# wooden_alarm_simple.net
KiCad netlist of a schematic drawn in EAGLE
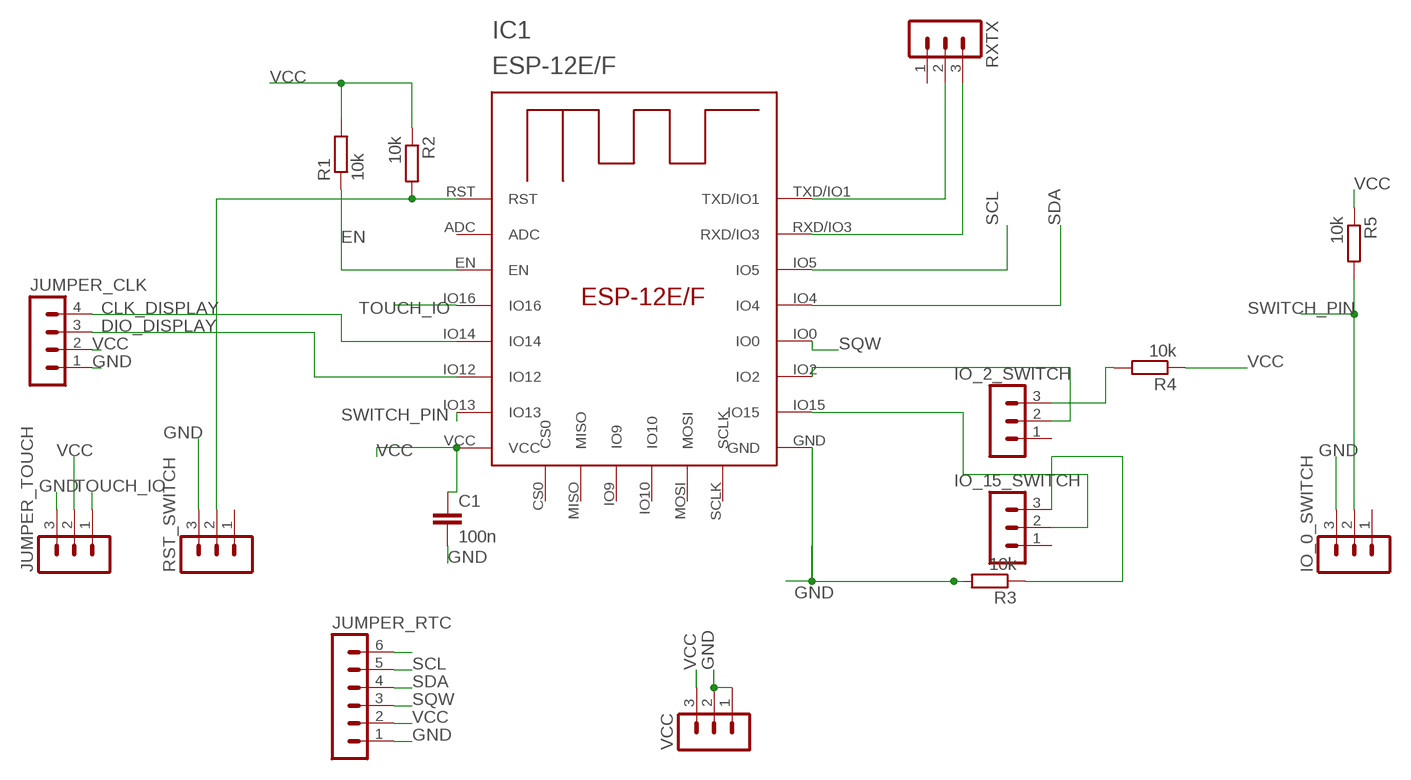
[diagram p0: schematic, sheet 1]

(export (version "E")
  (design (tool "Eeschema 10.0.6"))
  (components
    (comp (ref "C1")
      (value "100n")
      (footprint "eagle-import:C0805")
      (libsource (lib "eagle-import") (part "C-EUC0805"))
    )
    (comp (ref "IC1")
      (value "ESP-12E/F")
      (footprint "eagle-import:ESP-12E")
      (libsource (lib "eagle-import") (part "ESP-12E/F"))
    )
    (comp (ref "IO_0_SWITCH")
      (value "MA03-1")
      (footprint "eagle-import:MA03-1")
      (libsource (lib "eagle-import") (part "MA03-1"))
    )
    (comp (ref "IO_2_SWITCH")
      (value "MA03-1")
      (footprint "eagle-import:MA03-1")
      (libsource (lib "eagle-import") (part "MA03-1"))
    )
    (comp (ref "IO_15_SWITCH")
      (value "MA03-1")
      (footprint "eagle-import:MA03-1")
      (libsource (lib "eagle-import") (part "MA03-1"))
    )
    (comp (ref "JUMPER_CLK")
      (value "MA04-1")
      (footprint "eagle-import:MA04-1")
      (libsource (lib "eagle-import") (part "MA04-1"))
    )
    (comp (ref "JUMPER_RTC")
      (value "MA06-1")
      (footprint "eagle-import:MA06-1")
      (libsource (lib "eagle-import") (part "MA06-1"))
    )
    (comp (ref "JUMPER_TOUCH")
      (value "MA03-1")
      (footprint "eagle-import:MA03-1")
      (libsource (lib "eagle-import") (part "MA03-1"))
    )
    (comp (ref "R1")
      (value "10k")
      (footprint "eagle-import:R0805")
      (libsource (lib "eagle-import") (part "R-EU_R0805"))
    )
    (comp (ref "R2")
      (value "10k")
      (footprint "eagle-import:R0805")
      (libsource (lib "eagle-import") (part "R-EU_R0805"))
    )
    (comp (ref "R3")
      (value "10k")
      (footprint "eagle-import:R0805")
      (libsource (lib "eagle-import") (part "R-EU_R0805"))
    )
    (comp (ref "R4")
      (value "10k")
      (footprint "eagle-import:R0805")
      (libsource (lib "eagle-import") (part "R-EU_R0805"))
    )
    (comp (ref "R5")
      (value "10k")
      (footprint "eagle-import:R0805")
      (libsource (lib "eagle-import") (part "R-EU_R0805"))
    )
    (comp (ref "RST_SWITCH")
      (value "MA03-1")
      (footprint "eagle-import:MA03-1")
      (libsource (lib "eagle-import") (part "MA03-1"))
    )
    (comp (ref "RXTX")
      (value "MA03-1")
      (footprint "eagle-import:MA03-1")
      (libsource (lib "eagle-import") (part "MA03-1"))
    )
    (comp (ref "VCC")
      (value "MA03-1")
      (footprint "eagle-import:MA03-1")
      (libsource (lib "eagle-import") (part "MA03-1"))
    )
  )
  (nets
    (net (code "1") (name "/CLK_DISPLAY") (class "Default")
      (node (ref "IC1") (pin "IO14") (pinfunction "IO14_IO14") (pintype "bidirectional"))
      (node (ref "JUMPER_CLK") (pin "4") (pinfunction "4_4") (pintype "passive"))
    )
    (net (code "2") (name "/DIO_DISPLAY") (class "Default")
      (node (ref "IC1") (pin "IO12") (pinfunction "IO12_IO12") (pintype "bidirectional"))
      (node (ref "JUMPER_CLK") (pin "3") (pinfunction "3_3") (pintype "passive"))
    )
    (net (code "3") (name "/EN") (class "Default")
      (node (ref "IC1") (pin "EN") (pinfunction "EN_EN") (pintype "bidirectional"))
      (node (ref "R1") (pin "1") (pinfunction "1_1") (pintype "passive"))
    )
    (net (code "4") (name "/GND") (class "Default")
      (node (ref "C1") (pin "2") (pinfunction "2_2") (pintype "passive"))
      (node (ref "IC1") (pin "GND") (pinfunction "GND_GND") (pintype "power_in"))
      (node (ref "IO_0_SWITCH") (pin "3") (pinfunction "3_3") (pintype "passive"))
      (node (ref "JUMPER_CLK") (pin "1") (pinfunction "1_1") (pintype "passive"))
      (node (ref "JUMPER_RTC") (pin "1") (pinfunction "1_1") (pintype "passive"))
      (node (ref "JUMPER_TOUCH") (pin "3") (pinfunction "3_3") (pintype "passive"))
      (node (ref "R3") (pin "2") (pinfunction "2_2") (pintype "passive"))
      (node (ref "RST_SWITCH") (pin "3") (pinfunction "3_3") (pintype "passive"))
      (node (ref "VCC") (pin "1") (pinfunction "1_1") (pintype "passive"))
      (node (ref "VCC") (pin "2") (pinfunction "2_2") (pintype "passive"))
    )
    (net (code "5") (name "/SCL") (class "Default")
      (node (ref "IC1") (pin "IO5") (pinfunction "IO5_IO5") (pintype "bidirectional"))
      (node (ref "JUMPER_RTC") (pin "5") (pinfunction "5_5") (pintype "passive"))
    )
    (net (code "6") (name "/SDA") (class "Default")
      (node (ref "IC1") (pin "IO4") (pinfunction "IO4_IO4") (pintype "bidirectional"))
      (node (ref "JUMPER_RTC") (pin "4") (pinfunction "4_4") (pintype "passive"))
    )
    (net (code "7") (name "/SQW") (class "Default")
      (node (ref "IC1") (pin "IO0") (pinfunction "IO0_IO0") (pintype "bidirectional"))
      (node (ref "JUMPER_RTC") (pin "3") (pinfunction "3_3") (pintype "passive"))
    )
    (net (code "8") (name "/SWITCH_PIN") (class "Default")
      (node (ref "IC1") (pin "IO13") (pinfunction "IO13_IO13") (pintype "bidirectional"))
      (node (ref "IO_0_SWITCH") (pin "2") (pinfunction "2_2") (pintype "passive"))
      (node (ref "R5") (pin "2") (pinfunction "2_2") (pintype "passive"))
    )
    (net (code "9") (name "/TOUCH_IO") (class "Default")
      (node (ref "IC1") (pin "IO16") (pinfunction "IO16_IO16") (pintype "bidirectional"))
      (node (ref "JUMPER_TOUCH") (pin "1") (pinfunction "1_1") (pintype "passive"))
    )
    (net (code "10") (name "/VCC") (class "Default")
      (node (ref "C1") (pin "1") (pinfunction "1_1") (pintype "passive"))
      (node (ref "IC1") (pin "VCC") (pinfunction "VCC_VCC") (pintype "power_in"))
      (node (ref "JUMPER_CLK") (pin "2") (pinfunction "2_2") (pintype "passive"))
      (node (ref "JUMPER_RTC") (pin "2") (pinfunction "2_2") (pintype "passive"))
      (node (ref "JUMPER_TOUCH") (pin "2") (pinfunction "2_2") (pintype "passive"))
      (node (ref "R1") (pin "2") (pinfunction "2_2") (pintype "passive"))
      (node (ref "R2") (pin "1") (pinfunction "1_1") (pintype "passive"))
      (node (ref "R4") (pin "1") (pinfunction "1_1") (pintype "passive"))
      (node (ref "R5") (pin "1") (pinfunction "1_1") (pintype "passive"))
      (node (ref "VCC") (pin "3") (pinfunction "3_3") (pintype "passive"))
    )
    (net (code "11") (name "Net-(IC1-PadIO2)") (class "Default")
      (node (ref "IC1") (pin "IO2") (pinfunction "IO2_IO2") (pintype "bidirectional"))
      (node (ref "IO_2_SWITCH") (pin "2") (pinfunction "2_2") (pintype "passive"))
    )
    (net (code "12") (name "Net-(IC1-PadIO15)") (class "Default")
      (node (ref "IC1") (pin "IO15") (pinfunction "IO15_IO15") (pintype "bidirectional"))
      (node (ref "IO_15_SWITCH") (pin "2") (pinfunction "2_2") (pintype "passive"))
    )
    (net (code "13") (name "Net-(IC1-PadRST)") (class "Default")
      (node (ref "IC1") (pin "RST") (pinfunction "RST_RST") (pintype "input"))
      (node (ref "R2") (pin "2") (pinfunction "2_2") (pintype "passive"))
      (node (ref "RST_SWITCH") (pin "2") (pinfunction "2_2") (pintype "passive"))
    )
    (net (code "14") (name "Net-(IC1-PadRXD{slash}IO3)") (class "Default")
      (node (ref "IC1") (pin "RXD/IO3") (pinfunction "RXD/IO3_RXD/IO3") (pintype "bidirectional"))
      (node (ref "RXTX") (pin "3") (pinfunction "3_3") (pintype "passive"))
    )
    (net (code "15") (name "Net-(IC1-PadTXD{slash}IO1)") (class "Default")
      (node (ref "IC1") (pin "TXD/IO1") (pinfunction "TXD/IO1_TXD/IO1") (pintype "bidirectional"))
      (node (ref "RXTX") (pin "2") (pinfunction "2_2") (pintype "passive"))
    )
    (net (code "16") (name "Net-(IO_2_SWITCH-Pad3)") (class "Default")
      (node (ref "IO_2_SWITCH") (pin "3") (pinfunction "3_3") (pintype "passive"))
      (node (ref "R4") (pin "2") (pinfunction "2_2") (pintype "passive"))
    )
    (net (code "17") (name "Net-(IO_15_SWITCH-Pad3)") (class "Default")
      (node (ref "IO_15_SWITCH") (pin "3") (pinfunction "3_3") (pintype "passive"))
      (node (ref "R3") (pin "1") (pinfunction "1_1") (pintype "passive"))
    )
    (net (code "18") (name "unconnected-(IC1-PadADC)") (class "Default")
      (node (ref "IC1") (pin "ADC") (pinfunction "ADC_ADC") (pintype "bidirectional"))
    )
    (net (code "19") (name "unconnected-(IC1-PadCS0)") (class "Default")
      (node (ref "IC1") (pin "CS0") (pinfunction "CS0_CS0") (pintype "bidirectional"))
    )
    (net (code "20") (name "unconnected-(IC1-PadIO9)") (class "Default")
      (node (ref "IC1") (pin "IO9") (pinfunction "IO9_IO9") (pintype "bidirectional"))
    )
    (net (code "21") (name "unconnected-(IC1-PadIO10)") (class "Default")
      (node (ref "IC1") (pin "IO10") (pinfunction "IO10_IO10") (pintype "bidirectional"))
    )
    (net (code "22") (name "unconnected-(IC1-PadMISO)") (class "Default")
      (node (ref "IC1") (pin "MISO") (pinfunction "MISO_MISO") (pintype "bidirectional"))
    )
    (net (code "23") (name "unconnected-(IC1-PadMOSI)") (class "Default")
      (node (ref "IC1") (pin "MOSI") (pinfunction "MOSI_MOSI") (pintype "bidirectional"))
    )
    (net (code "24") (name "unconnected-(IC1-PadSCLK)") (class "Default")
      (node (ref "IC1") (pin "SCLK") (pinfunction "SCLK_SCLK") (pintype "bidirectional"))
    )
    (net (code "25") (name "unconnected-(IO_0_SWITCH-Pad1)") (class "Default")
      (node (ref "IO_0_SWITCH") (pin "1") (pinfunction "1_1") (pintype "passive"))
    )
    (net (code "26") (name "unconnected-(IO_2_SWITCH-Pad1)") (class "Default")
      (node (ref "IO_2_SWITCH") (pin "1") (pinfunction "1_1") (pintype "passive"))
    )
    (net (code "27") (name "unconnected-(IO_15_SWITCH-Pad1)") (class "Default")
      (node (ref "IO_15_SWITCH") (pin "1") (pinfunction "1_1") (pintype "passive"))
    )
    (net (code "28") (name "unconnected-(JUMPER_RTC-Pad6)") (class "Default")
      (node (ref "JUMPER_RTC") (pin "6") (pinfunction "6_6") (pintype "passive"))
    )
    (net (code "29") (name "unconnected-(RST_SWITCH-Pad1)") (class "Default")
      (node (ref "RST_SWITCH") (pin "1") (pinfunction "1_1") (pintype "passive"))
    )
    (net (code "30") (name "unconnected-(RXTX-Pad1)") (class "Default")
      (node (ref "RXTX") (pin "1") (pinfunction "1_1") (pintype "passive"))
    )
  )
)
